# relays.net
KiCad netlist of a schematic drawn in Altium Designer
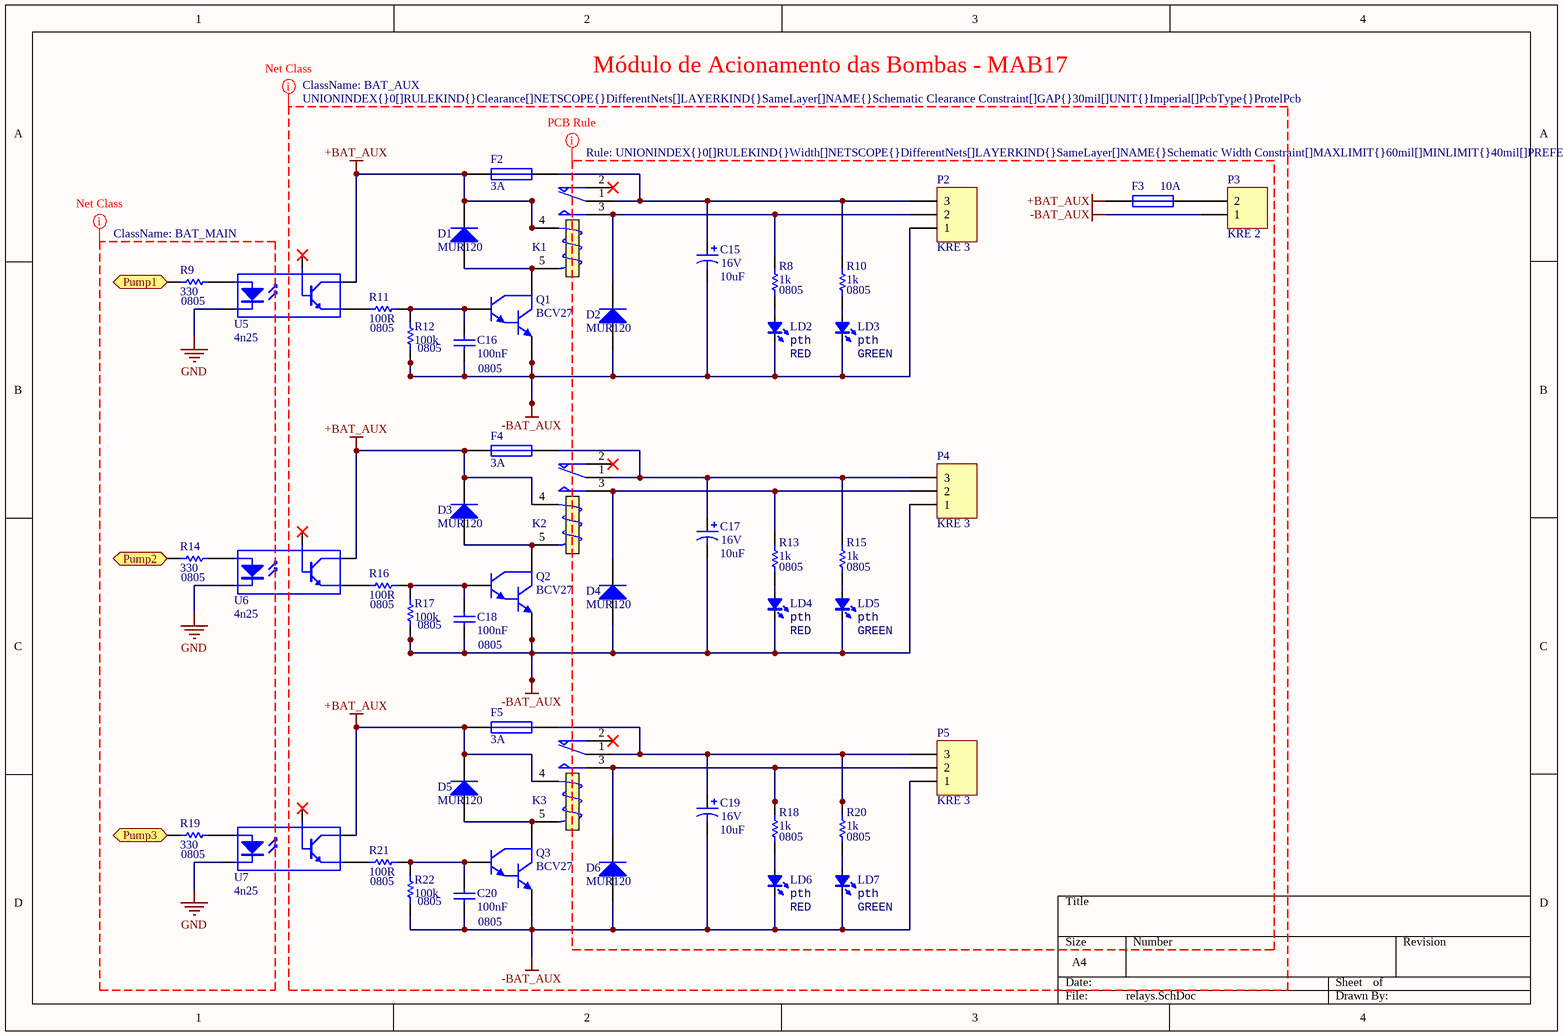
[diagram p0: relays.SchDoc]

(export (version "E")
  (design (tool "Eeschema 10.0.6"))
  (components
    (comp (ref "C15")
      (value "10uF")
      (footprint "cap10uF16V")
      (description "Polarized Capacitor (Radial)")
      (fields (field (name "VOLTAGE") "16V"))
      (libsource (lib "Miscellaneous Devices") (part "Cap Pol1"))
    )
    (comp (ref "C16")
      (value "100nF")
      (footprint "0805")
      (description "Capacitor")
      (fields (field (name "VOLTAGE") "25V"))
      (libsource (lib "Miscellaneous Devices") (part "Cap"))
    )
    (comp (ref "C17")
      (value "10uF")
      (footprint "cap10uF16V")
      (description "Polarized Capacitor (Radial)")
      (fields (field (name "VOLTAGE") "16V"))
      (libsource (lib "Miscellaneous Devices") (part "Cap Pol1"))
    )
    (comp (ref "C18")
      (value "100nF")
      (footprint "0805")
      (description "Capacitor")
      (fields (field (name "VOLTAGE") "25V"))
      (libsource (lib "Miscellaneous Devices") (part "Cap"))
    )
    (comp (ref "C19")
      (value "10uF")
      (footprint "cap10uF16V")
      (description "Polarized Capacitor (Radial)")
      (fields (field (name "VOLTAGE") "16V"))
      (libsource (lib "Miscellaneous Devices") (part "Cap Pol1"))
    )
    (comp (ref "C20")
      (value "100nF")
      (footprint "0805")
      (description "Capacitor")
      (fields (field (name "VOLTAGE") "25V"))
      (libsource (lib "Miscellaneous Devices") (part "Cap"))
    )
    (comp (ref "D1")
      (value "MUR120")
      (footprint "DIO10.2-7x2.7")
      (description "Default Diode")
      (libsource (lib "Miscellaneous Devices") (part "Diode"))
    )
    (comp (ref "D2")
      (value "MUR120")
      (footprint "DSO-C2/X2.3")
      (description "Default Diode")
      (libsource (lib "Miscellaneous Devices") (part "Diode"))
    )
    (comp (ref "D3")
      (value "MUR120")
      (footprint "DIO10.2-7x2.7")
      (description "Default Diode")
      (libsource (lib "Miscellaneous Devices") (part "Diode"))
    )
    (comp (ref "D4")
      (value "MUR120")
      (footprint "DSO-C2/X2.3")
      (description "Default Diode")
      (libsource (lib "Miscellaneous Devices") (part "Diode"))
    )
    (comp (ref "D5")
      (value "MUR120")
      (footprint "DIO10.2-7x2.7")
      (description "Default Diode")
      (libsource (lib "Miscellaneous Devices") (part "Diode"))
    )
    (comp (ref "D6")
      (value "MUR120")
      (footprint "DSO-C2/X2.3")
      (description "Default Diode")
      (libsource (lib "Miscellaneous Devices") (part "Diode"))
    )
    (comp (ref "F2")
      (value "3A")
      (footprint "Porta Fusivel")
      (description "Fuse 5x20")
      (libsource (lib "Miscellaneous Devices") (part "Fuse 1"))
    )
    (comp (ref "F3")
      (value "10A")
      (footprint "Porta Fusivel")
      (description "Fuse 5x20")
      (libsource (lib "Miscellaneous Devices") (part "Fuse 1"))
    )
    (comp (ref "F4")
      (value "3A")
      (footprint "Porta Fusivel")
      (description "Fuse 5x20")
      (libsource (lib "Miscellaneous Devices") (part "Fuse 1"))
    )
    (comp (ref "F5")
      (value "3A")
      (footprint "Porta Fusivel")
      (description "Fuse 5x20")
      (libsource (lib "Miscellaneous Devices") (part "Fuse 1"))
    )
    (comp (ref "K1")
      (value "~")
      (footprint "RELE")
      (description "SPDT Relay")
      (libsource (lib "Miscellaneous Devices") (part "Relay"))
    )
    (comp (ref "K2")
      (value "~")
      (footprint "RELE")
      (description "SPDT Relay")
      (libsource (lib "Miscellaneous Devices") (part "Relay"))
    )
    (comp (ref "K3")
      (value "~")
      (footprint "RELE")
      (description "SPDT Relay")
      (libsource (lib "Miscellaneous Devices") (part "Relay"))
    )
    (comp (ref "LD2")
      (value "RED")
      (footprint "LED3MM")
      (description "LED")
      (fields (field (name "TYPE") "pth"))
      (libsource (lib "SCH_Active") (part "LED_0805"))
    )
    (comp (ref "LD3")
      (value "GREEN")
      (footprint "LED3MM")
      (description "LED")
      (fields (field (name "TYPE") "pth"))
      (libsource (lib "SCH_Active") (part "LED_0805"))
    )
    (comp (ref "LD4")
      (value "RED")
      (footprint "LED3MM")
      (description "LED")
      (fields (field (name "TYPE") "pth"))
      (libsource (lib "SCH_Active") (part "LED_0805"))
    )
    (comp (ref "LD5")
      (value "GREEN")
      (footprint "LED3MM")
      (description "LED")
      (fields (field (name "TYPE") "pth"))
      (libsource (lib "SCH_Active") (part "LED_0805"))
    )
    (comp (ref "LD6")
      (value "RED")
      (footprint "LED3MM")
      (description "LED")
      (fields (field (name "TYPE") "pth"))
      (libsource (lib "SCH_Active") (part "LED_0805"))
    )
    (comp (ref "LD7")
      (value "GREEN")
      (footprint "LED3MM")
      (description "LED")
      (fields (field (name "TYPE") "pth"))
      (libsource (lib "SCH_Active") (part "LED_0805"))
    )
    (comp (ref "P2")
      (value "KRE 3")
      (footprint "KRE_3")
      (description "Header, 3-Pin")
      (libsource (lib "Miscellaneous Connectors") (part "Header 3"))
    )
    (comp (ref "P3")
      (value "KRE 2")
      (footprint "KRE_2")
      (description "Terminal Block 1x2")
      (libsource (lib "R2R - Nova") (part "KRE_2"))
    )
    (comp (ref "P4")
      (value "KRE 3")
      (footprint "KRE_3")
      (description "Header, 3-Pin")
      (libsource (lib "Miscellaneous Connectors") (part "Header 3"))
    )
    (comp (ref "P5")
      (value "KRE 3")
      (footprint "KRE_3")
      (description "Header, 3-Pin")
      (libsource (lib "Miscellaneous Connectors") (part "Header 3"))
    )
    (comp (ref "Q1")
      (value "BCV27")
      (footprint "SOT95P240-3N")
      (description "NPN Darlington Bipolar Transistor")
      (libsource (lib "Miscellaneous Devices") (part "NPN1"))
    )
    (comp (ref "Q2")
      (value "BCV27")
      (footprint "SOT95P240-3N")
      (description "NPN Darlington Bipolar Transistor")
      (libsource (lib "Miscellaneous Devices") (part "NPN1"))
    )
    (comp (ref "Q3")
      (value "BCV27")
      (footprint "SOT95P240-3N")
      (description "NPN Darlington Bipolar Transistor")
      (libsource (lib "Miscellaneous Devices") (part "NPN1"))
    )
    (comp (ref "R8")
      (value "1k")
      (footprint "0805R")
      (description "Resistor")
      (fields (field (name "TYPE") "0805"))
      (libsource (lib "Miscellaneous Devices") (part "Res1"))
    )
    (comp (ref "R9")
      (value "330")
      (footprint "0805R")
      (description "Resistor")
      (fields (field (name "TYPE") "0805"))
      (libsource (lib "Miscellaneous Devices") (part "Res1"))
    )
    (comp (ref "R10")
      (value "1k")
      (footprint "0805R")
      (description "Resistor")
      (fields (field (name "TYPE") "0805"))
      (libsource (lib "Miscellaneous Devices") (part "Res1"))
    )
    (comp (ref "R11")
      (value "100R")
      (footprint "0805R")
      (description "Resistor")
      (fields (field (name "TYPE") "0805"))
      (libsource (lib "Miscellaneous Devices") (part "Res1"))
    )
    (comp (ref "R12")
      (value "100k")
      (footprint "0805R")
      (description "Resistor")
      (fields (field (name "TYPE") "0805"))
      (libsource (lib "Miscellaneous Devices") (part "Res1"))
    )
    (comp (ref "R13")
      (value "1k")
      (footprint "0805R")
      (description "Resistor")
      (fields (field (name "TYPE") "0805"))
      (libsource (lib "Miscellaneous Devices") (part "Res1"))
    )
    (comp (ref "R14")
      (value "330")
      (footprint "0805R")
      (description "Resistor")
      (fields (field (name "TYPE") "0805"))
      (libsource (lib "Miscellaneous Devices") (part "Res1"))
    )
    (comp (ref "R15")
      (value "1k")
      (footprint "0805R")
      (description "Resistor")
      (fields (field (name "TYPE") "0805"))
      (libsource (lib "Miscellaneous Devices") (part "Res1"))
    )
    (comp (ref "R16")
      (value "100R")
      (footprint "0805C")
      (description "Resistor")
      (fields (field (name "TYPE") "0805"))
      (libsource (lib "Miscellaneous Devices") (part "Res1"))
    )
    (comp (ref "R17")
      (value "100k")
      (footprint "0805C")
      (description "Resistor")
      (fields (field (name "TYPE") "0805"))
      (libsource (lib "Miscellaneous Devices") (part "Res1"))
    )
    (comp (ref "R18")
      (value "1k")
      (footprint "0805R")
      (description "Resistor")
      (fields (field (name "TYPE") "0805"))
      (libsource (lib "Miscellaneous Devices") (part "Res1"))
    )
    (comp (ref "R19")
      (value "330")
      (footprint "0805R")
      (description "Resistor")
      (fields (field (name "TYPE") "0805"))
      (libsource (lib "Miscellaneous Devices") (part "Res1"))
    )
    (comp (ref "R20")
      (value "1k")
      (footprint "0805R")
      (description "Resistor")
      (fields (field (name "TYPE") "0805"))
      (libsource (lib "Miscellaneous Devices") (part "Res1"))
    )
    (comp (ref "R21")
      (value "100R")
      (footprint "0805C")
      (description "Resistor")
      (fields (field (name "TYPE") "0805"))
      (libsource (lib "Miscellaneous Devices") (part "Res1"))
    )
    (comp (ref "R22")
      (value "100k")
      (footprint "0805C")
      (description "Resistor")
      (fields (field (name "TYPE") "0805"))
      (libsource (lib "Miscellaneous Devices") (part "Res1"))
    )
    (comp (ref "U5")
      (value "4n25")
      (footprint "SMD-6")
      (description "5 Pin Mini Flat Pack Optocoupler")
      (libsource (lib "Miscellaneous Devices") (part "Optoisolator2"))
    )
    (comp (ref "U6")
      (value "4n25")
      (footprint "SMD-6")
      (description "5 Pin Mini Flat Pack Optocoupler")
      (libsource (lib "Miscellaneous Devices") (part "Optoisolator2"))
    )
    (comp (ref "U7")
      (value "4n25")
      (footprint "SMD-6")
      (description "5 Pin Mini Flat Pack Optocoupler")
      (libsource (lib "Miscellaneous Devices") (part "Optoisolator2"))
    )
  )
  (nets
    (net (code "1") (name "+BAT_AUX") (class "Default")
      (node (ref "D1") (pin "2") (pinfunction "K_2") (pintype "passive"))
      (node (ref "D3") (pin "2") (pinfunction "K_2") (pintype "passive"))
      (node (ref "D5") (pin "2") (pinfunction "K_2") (pintype "passive"))
      (node (ref "F2") (pin "2") (pinfunction "2_2") (pintype "passive"))
      (node (ref "F3") (pin "2") (pinfunction "2_2") (pintype "passive"))
      (node (ref "F4") (pin "2") (pinfunction "2_2") (pintype "passive"))
      (node (ref "F5") (pin "2") (pinfunction "2_2") (pintype "passive"))
      (node (ref "K1") (pin "4") (pinfunction "T1_4") (pintype "passive"))
      (node (ref "K2") (pin "4") (pinfunction "T1_4") (pintype "passive"))
      (node (ref "K3") (pin "4") (pinfunction "T1_4") (pintype "passive"))
      (node (ref "U5") (pin "5") (pinfunction "C_5") (pintype "passive"))
      (node (ref "U6") (pin "5") (pinfunction "C_5") (pintype "passive"))
      (node (ref "U7") (pin "5") (pinfunction "C_5") (pintype "passive"))
    )
    (net (code "2") (name "-BAT_AUX") (class "Default")
      (node (ref "C15") (pin "2") (pinfunction "2_2") (pintype "passive"))
      (node (ref "C16") (pin "1") (pinfunction "1_1") (pintype "passive"))
      (node (ref "C17") (pin "2") (pinfunction "2_2") (pintype "passive"))
      (node (ref "C18") (pin "1") (pinfunction "1_1") (pintype "passive"))
      (node (ref "C19") (pin "2") (pinfunction "2_2") (pintype "passive"))
      (node (ref "C20") (pin "1") (pinfunction "1_1") (pintype "passive"))
      (node (ref "D2") (pin "1") (pinfunction "A_1") (pintype "passive"))
      (node (ref "D4") (pin "1") (pinfunction "A_1") (pintype "passive"))
      (node (ref "D6") (pin "1") (pinfunction "A_1") (pintype "passive"))
      (node (ref "LD2") (pin "2") (pinfunction "K_2") (pintype "passive"))
      (node (ref "LD3") (pin "2") (pinfunction "K_2") (pintype "passive"))
      (node (ref "LD4") (pin "2") (pinfunction "K_2") (pintype "passive"))
      (node (ref "LD5") (pin "2") (pinfunction "K_2") (pintype "passive"))
      (node (ref "LD6") (pin "2") (pinfunction "K_2") (pintype "passive"))
      (node (ref "LD7") (pin "2") (pinfunction "K_2") (pintype "passive"))
      (node (ref "P2") (pin "1") (pinfunction "1_1") (pintype "passive"))
      (node (ref "P3") (pin "1") (pinfunction "1_1") (pintype "passive"))
      (node (ref "P4") (pin "1") (pinfunction "1_1") (pintype "passive"))
      (node (ref "P5") (pin "1") (pinfunction "1_1") (pintype "passive"))
      (node (ref "Q1") (pin "3") (pinfunction "E_3") (pintype "passive"))
      (node (ref "Q2") (pin "3") (pinfunction "E_3") (pintype "passive"))
      (node (ref "Q3") (pin "3") (pinfunction "E_3") (pintype "passive"))
      (node (ref "R12") (pin "1") (pinfunction "1_1") (pintype "passive"))
      (node (ref "R17") (pin "1") (pinfunction "1_1") (pintype "passive"))
      (node (ref "R22") (pin "1") (pinfunction "1_1") (pintype "passive"))
    )
    (net (code "3") (name "/Pump1") (class "Default")
      (node (ref "R9") (pin "1") (pinfunction "1_1") (pintype "passive"))
    )
    (net (code "4") (name "/Pump2") (class "Default")
      (node (ref "R14") (pin "1") (pinfunction "1_1") (pintype "passive"))
    )
    (net (code "5") (name "/Pump3") (class "Default")
      (node (ref "R19") (pin "1") (pinfunction "1_1") (pintype "passive"))
    )
    (net (code "6") (name "GND") (class "Default")
      (node (ref "U5") (pin "3") (pinfunction "K_3") (pintype "passive"))
      (node (ref "U6") (pin "3") (pinfunction "K_3") (pintype "passive"))
      (node (ref "U7") (pin "3") (pinfunction "K_3") (pintype "passive"))
    )
    (net (code "7") (name "Net-(D1-A)") (class "Default")
      (node (ref "D1") (pin "1") (pinfunction "A_1") (pintype "passive"))
      (node (ref "K1") (pin "5") (pinfunction "T2_5") (pintype "passive"))
      (node (ref "Q1") (pin "1") (pinfunction "C_1") (pintype "passive"))
    )
    (net (code "8") (name "Net-(D2-K)") (class "Default")
      (node (ref "D2") (pin "2") (pinfunction "K_2") (pintype "passive"))
      (node (ref "K1") (pin "3") (pinfunction "NO_3") (pintype "passive"))
      (node (ref "P2") (pin "2") (pinfunction "2_2") (pintype "passive"))
      (node (ref "R8") (pin "2") (pinfunction "2_2") (pintype "passive"))
    )
    (net (code "9") (name "Net-(D3-A)") (class "Default")
      (node (ref "D3") (pin "1") (pinfunction "A_1") (pintype "passive"))
      (node (ref "K2") (pin "5") (pinfunction "T2_5") (pintype "passive"))
      (node (ref "Q2") (pin "1") (pinfunction "C_1") (pintype "passive"))
    )
    (net (code "10") (name "Net-(D4-K)") (class "Default")
      (node (ref "D4") (pin "2") (pinfunction "K_2") (pintype "passive"))
      (node (ref "K2") (pin "3") (pinfunction "NO_3") (pintype "passive"))
      (node (ref "P4") (pin "2") (pinfunction "2_2") (pintype "passive"))
      (node (ref "R13") (pin "2") (pinfunction "2_2") (pintype "passive"))
    )
    (net (code "11") (name "Net-(D5-A)") (class "Default")
      (node (ref "D5") (pin "1") (pinfunction "A_1") (pintype "passive"))
      (node (ref "K3") (pin "5") (pinfunction "T2_5") (pintype "passive"))
      (node (ref "Q3") (pin "1") (pinfunction "C_1") (pintype "passive"))
    )
    (net (code "12") (name "Net-(D6-K)") (class "Default")
      (node (ref "D6") (pin "2") (pinfunction "K_2") (pintype "passive"))
      (node (ref "K3") (pin "3") (pinfunction "NO_3") (pintype "passive"))
      (node (ref "P5") (pin "2") (pinfunction "2_2") (pintype "passive"))
      (node (ref "R18") (pin "2") (pinfunction "2_2") (pintype "passive"))
    )
    (net (code "13") (name "Net-(F3-Pad1)") (class "Default")
      (node (ref "F3") (pin "1") (pinfunction "1_1") (pintype "passive"))
      (node (ref "P3") (pin "2") (pinfunction "2_2") (pintype "passive"))
    )
    (net (code "14") (name "Net-(K1-COM)") (class "Default")
      (node (ref "C15") (pin "1") (pinfunction "1_1") (pintype "passive"))
      (node (ref "F2") (pin "1") (pinfunction "1_1") (pintype "passive"))
      (node (ref "K1") (pin "1") (pinfunction "COM_1") (pintype "passive"))
      (node (ref "P2") (pin "3") (pinfunction "3_3") (pintype "passive"))
      (node (ref "R10") (pin "2") (pinfunction "2_2") (pintype "passive"))
    )
    (net (code "15") (name "Net-(K2-COM)") (class "Default")
      (node (ref "C17") (pin "1") (pinfunction "1_1") (pintype "passive"))
      (node (ref "F4") (pin "1") (pinfunction "1_1") (pintype "passive"))
      (node (ref "K2") (pin "1") (pinfunction "COM_1") (pintype "passive"))
      (node (ref "P4") (pin "3") (pinfunction "3_3") (pintype "passive"))
      (node (ref "R15") (pin "2") (pinfunction "2_2") (pintype "passive"))
    )
    (net (code "16") (name "Net-(K3-COM)") (class "Default")
      (node (ref "C19") (pin "1") (pinfunction "1_1") (pintype "passive"))
      (node (ref "F5") (pin "1") (pinfunction "1_1") (pintype "passive"))
      (node (ref "K3") (pin "1") (pinfunction "COM_1") (pintype "passive"))
      (node (ref "P5") (pin "3") (pinfunction "3_3") (pintype "passive"))
      (node (ref "R20") (pin "2") (pinfunction "2_2") (pintype "passive"))
    )
    (net (code "17") (name "Net-(LD2-A)") (class "Default")
      (node (ref "LD2") (pin "1") (pinfunction "A_1") (pintype "passive"))
      (node (ref "R8") (pin "1") (pinfunction "1_1") (pintype "passive"))
    )
    (net (code "18") (name "Net-(LD3-A)") (class "Default")
      (node (ref "LD3") (pin "1") (pinfunction "A_1") (pintype "passive"))
      (node (ref "R10") (pin "1") (pinfunction "1_1") (pintype "passive"))
    )
    (net (code "19") (name "Net-(LD4-A)") (class "Default")
      (node (ref "LD4") (pin "1") (pinfunction "A_1") (pintype "passive"))
      (node (ref "R13") (pin "1") (pinfunction "1_1") (pintype "passive"))
    )
    (net (code "20") (name "Net-(LD5-A)") (class "Default")
      (node (ref "LD5") (pin "1") (pinfunction "A_1") (pintype "passive"))
      (node (ref "R15") (pin "1") (pinfunction "1_1") (pintype "passive"))
    )
    (net (code "21") (name "Net-(LD6-A)") (class "Default")
      (node (ref "LD6") (pin "1") (pinfunction "A_1") (pintype "passive"))
      (node (ref "R18") (pin "1") (pinfunction "1_1") (pintype "passive"))
    )
    (net (code "22") (name "Net-(LD7-A)") (class "Default")
      (node (ref "LD7") (pin "1") (pinfunction "A_1") (pintype "passive"))
      (node (ref "R20") (pin "1") (pinfunction "1_1") (pintype "passive"))
    )
    (net (code "23") (name "Net-(Q1-B)") (class "Default")
      (node (ref "C16") (pin "2") (pinfunction "2_2") (pintype "passive"))
      (node (ref "Q1") (pin "2") (pinfunction "B_2") (pintype "passive"))
      (node (ref "R11") (pin "1") (pinfunction "1_1") (pintype "passive"))
      (node (ref "R12") (pin "2") (pinfunction "2_2") (pintype "passive"))
    )
    (net (code "24") (name "Net-(Q2-B)") (class "Default")
      (node (ref "C18") (pin "2") (pinfunction "2_2") (pintype "passive"))
      (node (ref "Q2") (pin "2") (pinfunction "B_2") (pintype "passive"))
      (node (ref "R16") (pin "1") (pinfunction "1_1") (pintype "passive"))
      (node (ref "R17") (pin "2") (pinfunction "2_2") (pintype "passive"))
    )
    (net (code "25") (name "Net-(Q3-B)") (class "Default")
      (node (ref "C20") (pin "2") (pinfunction "2_2") (pintype "passive"))
      (node (ref "Q3") (pin "2") (pinfunction "B_2") (pintype "passive"))
      (node (ref "R21") (pin "1") (pinfunction "1_1") (pintype "passive"))
      (node (ref "R22") (pin "2") (pinfunction "2_2") (pintype "passive"))
    )
    (net (code "26") (name "Net-(U5-A)") (class "Default")
      (node (ref "R9") (pin "2") (pinfunction "2_2") (pintype "passive"))
      (node (ref "U5") (pin "1") (pinfunction "A_1") (pintype "passive"))
    )
    (net (code "27") (name "Net-(U5-E)") (class "Default")
      (node (ref "R11") (pin "2") (pinfunction "2_2") (pintype "passive"))
      (node (ref "U5") (pin "4") (pinfunction "E_4") (pintype "passive"))
    )
    (net (code "28") (name "Net-(U6-A)") (class "Default")
      (node (ref "R14") (pin "2") (pinfunction "2_2") (pintype "passive"))
      (node (ref "U6") (pin "1") (pinfunction "A_1") (pintype "passive"))
    )
    (net (code "29") (name "Net-(U6-E)") (class "Default")
      (node (ref "R16") (pin "2") (pinfunction "2_2") (pintype "passive"))
      (node (ref "U6") (pin "4") (pinfunction "E_4") (pintype "passive"))
    )
    (net (code "30") (name "Net-(U7-A)") (class "Default")
      (node (ref "R19") (pin "2") (pinfunction "2_2") (pintype "passive"))
      (node (ref "U7") (pin "1") (pinfunction "A_1") (pintype "passive"))
    )
    (net (code "31") (name "Net-(U7-E)") (class "Default")
      (node (ref "R21") (pin "2") (pinfunction "2_2") (pintype "passive"))
      (node (ref "U7") (pin "4") (pinfunction "E_4") (pintype "passive"))
    )
    (net (code "32") (name "unconnected-(K1-NC-Pad2)") (class "Default")
      (node (ref "K1") (pin "2") (pinfunction "NC_2") (pintype "passive+no_connect"))
    )
    (net (code "33") (name "unconnected-(K2-NC-Pad2)") (class "Default")
      (node (ref "K2") (pin "2") (pinfunction "NC_2") (pintype "passive+no_connect"))
    )
    (net (code "34") (name "unconnected-(K3-NC-Pad2)") (class "Default")
      (node (ref "K3") (pin "2") (pinfunction "NC_2") (pintype "passive+no_connect"))
    )
    (net (code "35") (name "unconnected-(U5-B-Pad6)") (class "Default")
      (node (ref "U5") (pin "6") (pinfunction "B_6") (pintype "passive+no_connect"))
    )
    (net (code "36") (name "unconnected-(U6-B-Pad6)") (class "Default")
      (node (ref "U6") (pin "6") (pinfunction "B_6") (pintype "passive+no_connect"))
    )
    (net (code "37") (name "unconnected-(U7-B-Pad6)") (class "Default")
      (node (ref "U7") (pin "6") (pinfunction "B_6") (pintype "passive+no_connect"))
    )
  )
)
